# Cap-Touch-Keypad-REG-v1_0.net
KiCad netlist of a schematic drawn in EAGLE
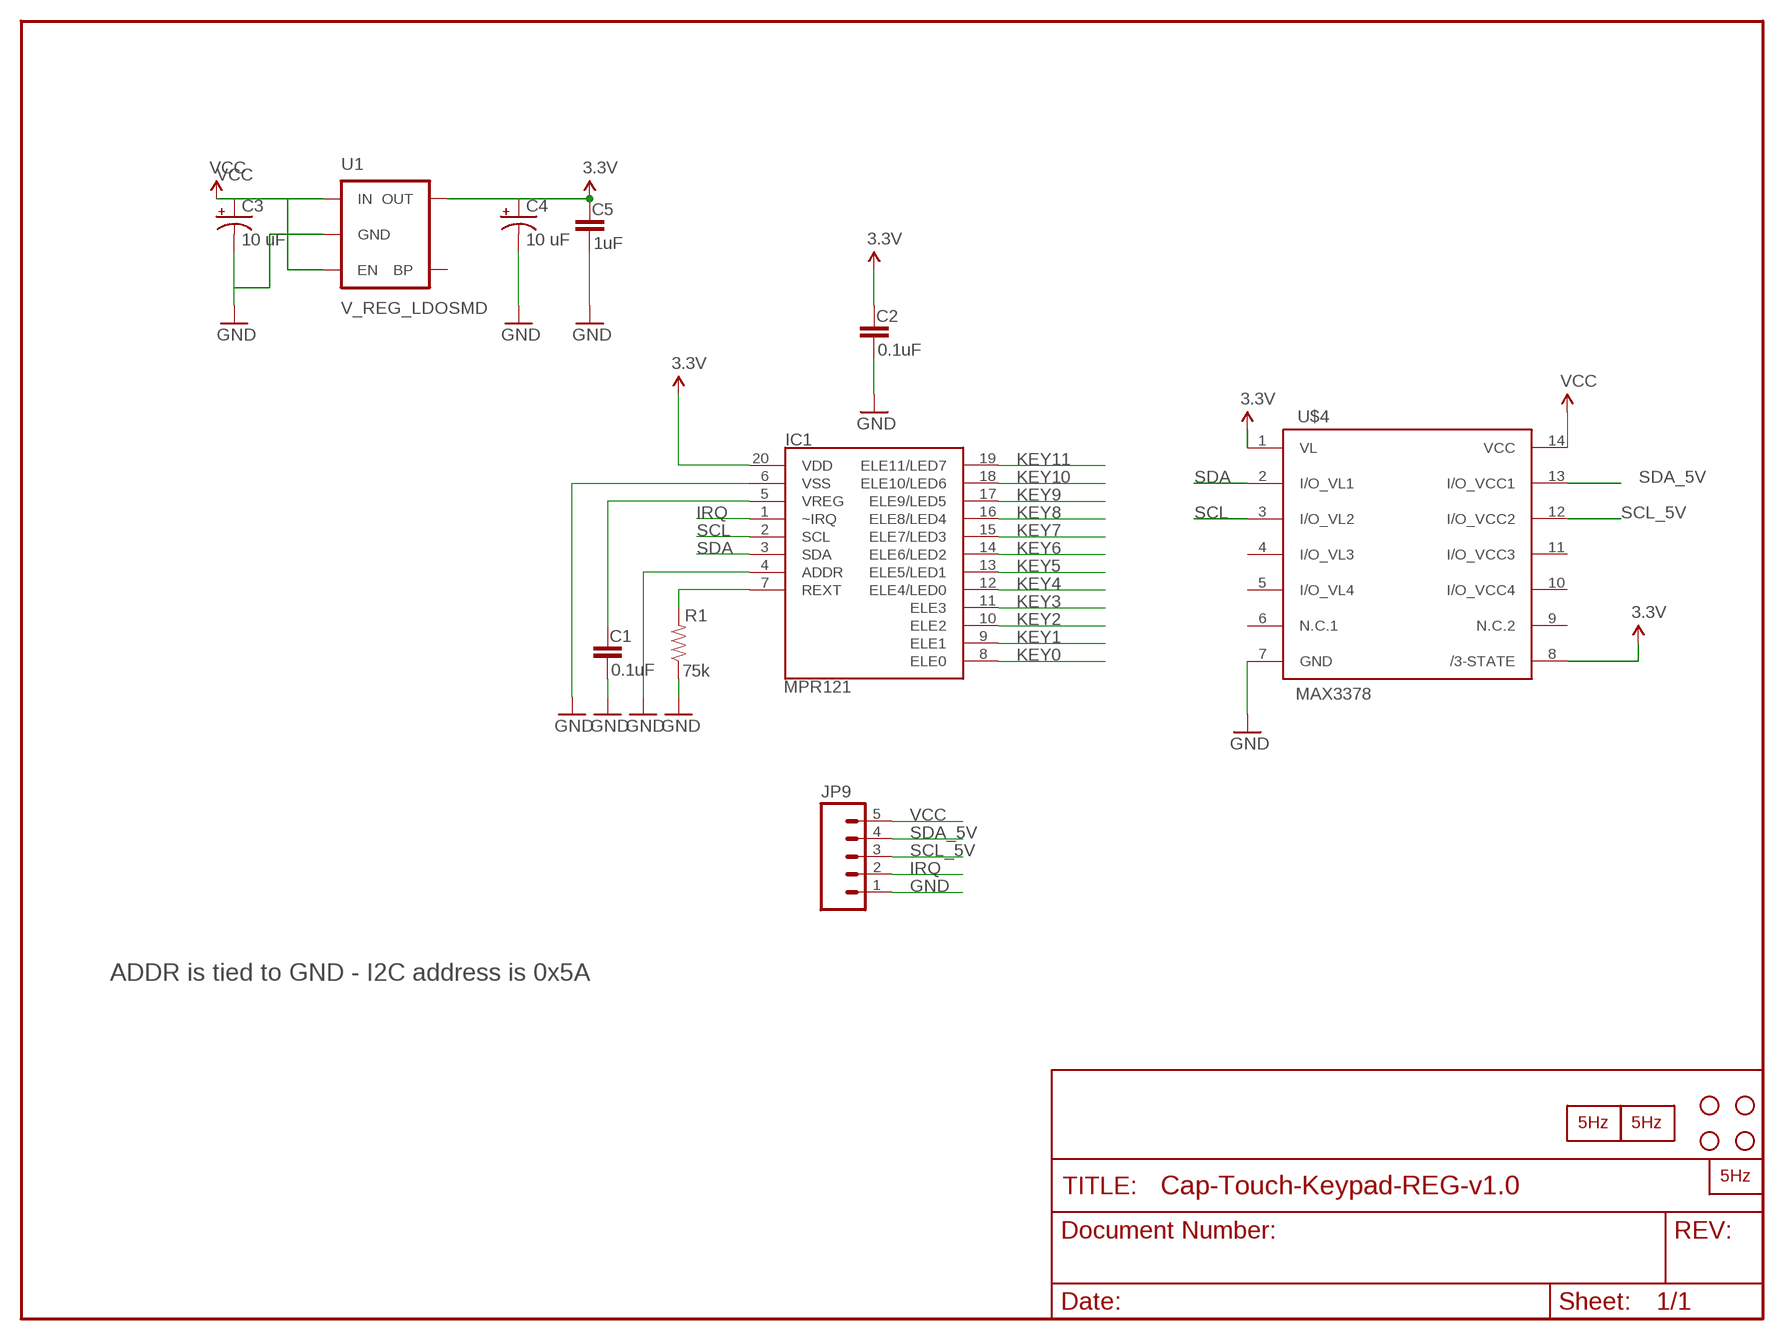
[diagram p0: schematic, sheet 1]

(export (version "E")
  (design (tool "Eeschema 10.0.6"))
  (components
    (comp (ref "C1")
      (value "0.1uF")
      (footprint "eagle-import:0402-CAP")
      (libsource (lib "eagle-import") (part "CAP0402-CAP"))
    )
    (comp (ref "C2")
      (value "0.1uF")
      (footprint "eagle-import:0402-CAP")
      (libsource (lib "eagle-import") (part "CAP0402-CAP"))
    )
    (comp (ref "C3")
      (value "10 uF")
      (footprint "eagle-import:EIA3216")
      (libsource (lib "eagle-import") (part "CAP_POL1206"))
    )
    (comp (ref "C4")
      (value "10 uF")
      (footprint "eagle-import:EIA3216")
      (libsource (lib "eagle-import") (part "CAP_POL1206"))
    )
    (comp (ref "C5")
      (value "1uF")
      (footprint "eagle-import:0402-CAP")
      (libsource (lib "eagle-import") (part "CAP0402-CAP"))
    )
    (comp (ref "IC1")
      (value "MPR121")
      (footprint "eagle-import:QFN-20-0.4MM")
      (libsource (lib "eagle-import") (part "MPR121QFN20"))
    )
    (comp (ref "JP3")
      (value "STAND-OFF")
      (footprint "eagle-import:STAND-OFF")
      (libsource (lib "eagle-import") (part "STAND-OFF"))
    )
    (comp (ref "JP4")
      (value "STAND-OFF")
      (footprint "eagle-import:STAND-OFF")
      (libsource (lib "eagle-import") (part "STAND-OFF"))
    )
    (comp (ref "JP7")
      (value "STAND-OFF")
      (footprint "eagle-import:STAND-OFF")
      (libsource (lib "eagle-import") (part "STAND-OFF"))
    )
    (comp (ref "JP8")
      (value "STAND-OFF")
      (footprint "eagle-import:STAND-OFF")
      (libsource (lib "eagle-import") (part "STAND-OFF"))
    )
    (comp (ref "JP9")
      (value "M05PTH")
      (footprint "eagle-import:1X05")
      (libsource (lib "eagle-import") (part "M05PTH"))
    )
    (comp (ref "R1")
      (value "75k")
      (footprint "eagle-import:0402-RES")
      (libsource (lib "eagle-import") (part "RESISTOR0402-RES"))
    )
    (comp (ref "U$1")
      (value "LOGO2_SILKL20MM")
      (footprint "eagle-import:LARGO2_20MM")
      (libsource (lib "eagle-import") (part "LOGO2_SILKL20MM"))
    )
    (comp (ref "U$2")
      (value "LOGO2_SILKC5MM")
      (footprint "eagle-import:CIRCULO2_5MM")
      (libsource (lib "eagle-import") (part "LOGO2_SILKC5MM"))
    )
    (comp (ref "U$3")
      (value "LOGO2_SILKC5MM")
      (footprint "eagle-import:CIRCULO2_5MM")
      (libsource (lib "eagle-import") (part "LOGO2_SILKC5MM"))
    )
    (comp (ref "U$4")
      (value "MAX3378")
      (footprint "eagle-import:TSSOP14")
      (libsource (lib "eagle-import") (part "MAX3378"))
    )
    (comp (ref "U1")
      (value "V_REG_LDOSMD")
      (footprint "eagle-import:SOT23-5")
      (libsource (lib "eagle-import") (part "V_REG_LDOSMD"))
    )
  )
  (nets
    (net (code "1") (name "/IRQ") (class "Default")
      (node (ref "IC1") (pin "1") (pinfunction "~{IRQ}_1") (pintype "bidirectional"))
      (node (ref "JP9") (pin "2") (pinfunction "2_2") (pintype "passive"))
    )
    (net (code "2") (name "/KEY0") (class "Default")
      (node (ref "IC1") (pin "8") (pinfunction "ELE0_8") (pintype "bidirectional"))
    )
    (net (code "3") (name "/KEY1") (class "Default")
      (node (ref "IC1") (pin "9") (pinfunction "ELE1_9") (pintype "bidirectional"))
    )
    (net (code "4") (name "/KEY2") (class "Default")
      (node (ref "IC1") (pin "10") (pinfunction "ELE2_10") (pintype "bidirectional"))
    )
    (net (code "5") (name "/KEY3") (class "Default")
      (node (ref "IC1") (pin "11") (pinfunction "ELE3_11") (pintype "bidirectional"))
    )
    (net (code "6") (name "/KEY4") (class "Default")
      (node (ref "IC1") (pin "12") (pinfunction "ELE4/LED0_12") (pintype "bidirectional"))
    )
    (net (code "7") (name "/KEY5") (class "Default")
      (node (ref "IC1") (pin "13") (pinfunction "ELE5/LED1_13") (pintype "bidirectional"))
    )
    (net (code "8") (name "/KEY6") (class "Default")
      (node (ref "IC1") (pin "14") (pinfunction "ELE6/LED2_14") (pintype "bidirectional"))
    )
    (net (code "9") (name "/KEY7") (class "Default")
      (node (ref "IC1") (pin "15") (pinfunction "ELE7/LED3_15") (pintype "bidirectional"))
    )
    (net (code "10") (name "/KEY8") (class "Default")
      (node (ref "IC1") (pin "16") (pinfunction "ELE8/LED4_16") (pintype "bidirectional"))
    )
    (net (code "11") (name "/KEY9") (class "Default")
      (node (ref "IC1") (pin "17") (pinfunction "ELE9/LED5_17") (pintype "bidirectional"))
    )
    (net (code "12") (name "/KEY10") (class "Default")
      (node (ref "IC1") (pin "18") (pinfunction "ELE10/LED6_18") (pintype "bidirectional"))
    )
    (net (code "13") (name "/KEY11") (class "Default")
      (node (ref "IC1") (pin "19") (pinfunction "ELE11/LED7_19") (pintype "bidirectional"))
    )
    (net (code "14") (name "/SCL") (class "Default")
      (node (ref "IC1") (pin "2") (pinfunction "SCL_2") (pintype "bidirectional"))
      (node (ref "U$4") (pin "3") (pinfunction "I/O_VL2_3") (pintype "bidirectional"))
    )
    (net (code "15") (name "/SCL_5V") (class "Default")
      (node (ref "JP9") (pin "3") (pinfunction "3_3") (pintype "passive"))
      (node (ref "U$4") (pin "12") (pinfunction "I/O_VCC2_12") (pintype "bidirectional"))
    )
    (net (code "16") (name "/SDA") (class "Default")
      (node (ref "IC1") (pin "3") (pinfunction "SDA_3") (pintype "bidirectional"))
      (node (ref "U$4") (pin "2") (pinfunction "I/O_VL1_2") (pintype "bidirectional"))
    )
    (net (code "17") (name "/SDA_5V") (class "Default")
      (node (ref "JP9") (pin "4") (pinfunction "4_4") (pintype "passive"))
      (node (ref "U$4") (pin "13") (pinfunction "I/O_VCC1_13") (pintype "bidirectional"))
    )
    (net (code "18") (name "3.3V") (class "Default")
      (node (ref "C2") (pin "1") (pinfunction "1_1") (pintype "passive"))
      (node (ref "C4") (pin "A") (pinfunction "+_A") (pintype "passive"))
      (node (ref "C5") (pin "1") (pinfunction "1_1") (pintype "passive"))
      (node (ref "IC1") (pin "20") (pinfunction "VDD_20") (pintype "bidirectional"))
      (node (ref "U$4") (pin "1") (pinfunction "VL_1") (pintype "bidirectional"))
      (node (ref "U$4") (pin "8") (pinfunction "/3-STATE_8") (pintype "bidirectional"))
      (node (ref "U1") (pin "5") (pinfunction "OUT_5") (pintype "passive"))
    )
    (net (code "19") (name "GND") (class "Default")
      (node (ref "C1") (pin "2") (pinfunction "2_2") (pintype "passive"))
      (node (ref "C2") (pin "2") (pinfunction "2_2") (pintype "passive"))
      (node (ref "C3") (pin "C") (pinfunction "-_C") (pintype "passive"))
      (node (ref "C4") (pin "C") (pinfunction "-_C") (pintype "passive"))
      (node (ref "C5") (pin "2") (pinfunction "2_2") (pintype "passive"))
      (node (ref "IC1") (pin "4") (pinfunction "ADDR_4") (pintype "bidirectional"))
      (node (ref "IC1") (pin "6") (pinfunction "VSS_6") (pintype "bidirectional"))
      (node (ref "JP9") (pin "1") (pinfunction "1_1") (pintype "passive"))
      (node (ref "R1") (pin "1") (pinfunction "1_1") (pintype "passive"))
      (node (ref "U$4") (pin "7") (pinfunction "GND_7") (pintype "bidirectional"))
      (node (ref "U1") (pin "2") (pinfunction "GND_2") (pintype "input"))
    )
    (net (code "20") (name "Net-(IC1-REXT)") (class "Default")
      (node (ref "IC1") (pin "7") (pinfunction "REXT_7") (pintype "bidirectional"))
      (node (ref "R1") (pin "2") (pinfunction "2_2") (pintype "passive"))
    )
    (net (code "21") (name "Net-(IC1-VREG)") (class "Default")
      (node (ref "C1") (pin "1") (pinfunction "1_1") (pintype "passive"))
      (node (ref "IC1") (pin "5") (pinfunction "VREG_5") (pintype "bidirectional"))
    )
    (net (code "22") (name "VCC") (class "Default")
      (node (ref "C3") (pin "A") (pinfunction "+_A") (pintype "passive"))
      (node (ref "JP9") (pin "5") (pinfunction "5_5") (pintype "passive"))
      (node (ref "U$4") (pin "14") (pinfunction "VCC_14") (pintype "bidirectional"))
      (node (ref "U1") (pin "1") (pinfunction "IN_1") (pintype "input"))
      (node (ref "U1") (pin "3") (pinfunction "EN_3") (pintype "input"))
    )
    (net (code "23") (name "unconnected-(U$4-I{slash}O_VCC3-Pad11)") (class "Default")
      (node (ref "U$4") (pin "11") (pinfunction "I/O_VCC3_11") (pintype "bidirectional"))
    )
    (net (code "24") (name "unconnected-(U$4-I{slash}O_VCC4-Pad10)") (class "Default")
      (node (ref "U$4") (pin "10") (pinfunction "I/O_VCC4_10") (pintype "bidirectional"))
    )
    (net (code "25") (name "unconnected-(U$4-I{slash}O_VL3-Pad4)") (class "Default")
      (node (ref "U$4") (pin "4") (pinfunction "I/O_VL3_4") (pintype "bidirectional"))
    )
    (net (code "26") (name "unconnected-(U$4-I{slash}O_VL4-Pad5)") (class "Default")
      (node (ref "U$4") (pin "5") (pinfunction "I/O_VL4_5") (pintype "bidirectional"))
    )
    (net (code "27") (name "unconnected-(U$4-N.C.1-Pad6)") (class "Default")
      (node (ref "U$4") (pin "6") (pinfunction "N.C.1_6") (pintype "bidirectional"))
    )
    (net (code "28") (name "unconnected-(U$4-N.C.2-Pad9)") (class "Default")
      (node (ref "U$4") (pin "9") (pinfunction "N.C.2_9") (pintype "bidirectional"))
    )
    (net (code "29") (name "unconnected-(U1-BP-Pad4)") (class "Default")
      (node (ref "U1") (pin "4") (pinfunction "BP_4") (pintype "input"))
    )
  )
)
